# Sheet1.net
KiCad netlist of a schematic drawn in Altium Designer
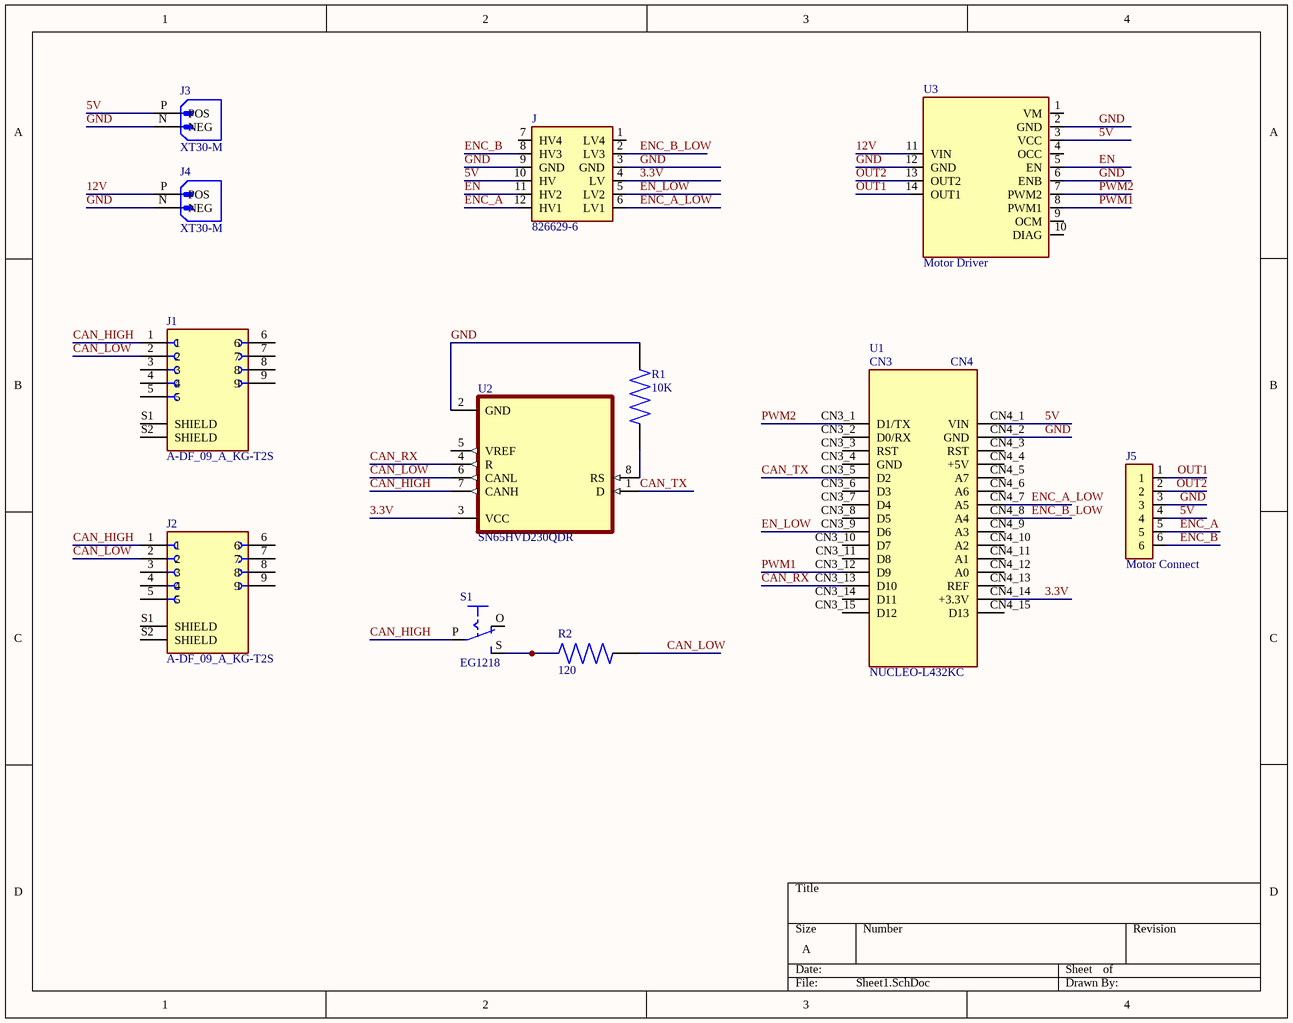
[diagram p0: Sheet1.SchDoc]

(export (version "E")
  (design (tool "Eeschema 10.0.6"))
  (components
    (comp (ref "J")
      (value "826629-6")
      (footprint "Level Converter:HDRV6W63P254_6X1_1524X250X950")
      (description "Conn Unshrouded Header HDR 6 POS 2.54mm Solder ST Thru-Hole Automotive Carton")
      (fields (field (name "MF") "TE Connectivity"))
      (libsource (lib "Level Converter") (part "826629-6"))
    )
    (comp (ref "J1")
      (value "A-DF_09_A_KG-T2S")
      (footprint "ASSMANN_A-DF_09_A_KG-T2S")
      (description "9 Position D-Sub Receptacle, Female Sockets Connector")
      (fields (field (name "MF") "Assmann WSW") (field (name "MP") "A-DF 09 A/KG-T2S"))
      (libsource (lib "A-DF_09_A_KG-T2S") (part "A-DF_09_A_KG-T2S"))
    )
    (comp (ref "J2")
      (value "A-DF_09_A_KG-T2S")
      (footprint "ASSMANN_A-DF_09_A_KG-T2S")
      (description "9 Position D-Sub Receptacle, Female Sockets Connector")
      (fields (field (name "MF") "Assmann WSW") (field (name "MP") "A-DF 09 A/KG-T2S"))
      (libsource (lib "A-DF_09_A_KG-T2S") (part "A-DF_09_A_KG-T2S"))
    )
    (comp (ref "J3")
      (value "XT30-M")
      (footprint "AMASS_XT60-M")
      (description "Plug; DC supply; XT60; male; PIN: 2; for cable; soldered; 30A; 500V")
      (fields (field (name "MP") "XT60-M") (field (name "MF") "AMASS"))
      (libsource (lib "XT30-M") (part "XT30-M"))
    )
    (comp (ref "J4")
      (value "XT30-M")
      (footprint "AMASS_XT60-M")
      (description "Plug; DC supply; XT60; male; PIN: 2; for cable; soldered; 30A; 500V")
      (fields (field (name "MP") "XT60-M") (field (name "MF") "AMASS"))
      (libsource (lib "XT30-M") (part "XT30-M"))
    )
    (comp (ref "J5")
      (value "Motor Connect")
      (footprint "HDRV6W63P254_6X1_1524X250X950")
      (description "Conn Unshrouded Header HDR 6 POS 2.54mm Solder ST Thru-Hole Automotive Carton")
      (fields (field (name "MP") "826629-6") (field (name "MF") "TE Connectivity"))
      (libsource (lib "826629-6") (part "826629-6"))
    )
    (comp (ref "R1")
      (value "10K")
      (footprint "RESC3216X65N:RESC3216X65N")
      (fields (field (name "MP") "KTR18EZPF9530"))
      (libsource (lib "KTR18EZPF9530") (part "KTR18EZPF9530"))
    )
    (comp (ref "R2")
      (value "120")
      (footprint "RESC3216X65N:RESC3216X65N")
      (fields (field (name "MP") "KTR18EZPF9530"))
      (libsource (lib "KTR18EZPF9530") (part "KTR18EZPF9530"))
    )
    (comp (ref "S1") (value "EG1218") (footprint "EG1218:EG1218") (libsource (lib "EG1218") (part "EG1218")))
    (comp (ref "U1")
      (value "NUCLEO-L432KC")
      (footprint "MODULE_NUCLEO-L432KC")
      (description "STM32 Nucleo-32 development board with STM32L432KC MCU, supports Arduino connectivity")
      (libsource (lib "NUCLEO-L432KC") (part "NUCLEO-L432KC"))
    )
    (comp (ref "U2")
      (value "SN65HVD230QDR")
      (footprint "SOIC127P599X175-8N")
      (description "3.3-V CAN Transceiver with Standby Mode 8-SOIC -40 to 125")
      (fields (field (name "MF") "Texas Instruments"))
      (libsource (lib "SN65HVD230QDR") (part "SN65HVD230QDR"))
    )
    (comp (ref "U3")
      (value "Motor Driver")
      (footprint "SnapEDApcb:TE_826629-8")
      (description "Conn Unshrouded Header HDR 8 POS 2.54mm Solder ST Thru-Hole Automotive Box")
      (fields (field (name "MP") "826629-8") (field (name "MF") "TE Connectivity"))
      (libsource (lib "Pololu Motor Driver") (part "826629-8"))
    )
  )
  (nets
    (net (code "1") (name "/3.3V") (class "Default")
      (node (ref "J") (pin "4") (pinfunction "LV_4") (pintype "passive"))
      (node (ref "U1") (pin "CN4_14") (pinfunction "+3.3V_CN4_14") (pintype "power_in"))
      (node (ref "U2") (pin "3") (pinfunction "VCC_3") (pintype "power_in"))
    )
    (net (code "2") (name "/5V") (class "Default")
      (node (ref "J") (pin "10") (pinfunction "HV_10") (pintype "passive"))
      (node (ref "J3") (pin "P") (pinfunction "POS_P") (pintype "passive"))
      (node (ref "J5") (pin "4") (pinfunction "4_4") (pintype "passive"))
      (node (ref "U1") (pin "CN4_1") (pinfunction "VIN_CN4_1") (pintype "power_in"))
      (node (ref "U3") (pin "3") (pinfunction "VCC_3") (pintype "passive"))
    )
    (net (code "3") (name "/12V") (class "Default")
      (node (ref "J4") (pin "P") (pinfunction "POS_P") (pintype "passive"))
      (node (ref "U3") (pin "11") (pinfunction "VIN_11") (pintype "passive"))
    )
    (net (code "4") (name "/CAN_HIGH") (class "Default")
      (node (ref "J1") (pin "1") (pinfunction "1_1") (pintype "passive"))
      (node (ref "J2") (pin "1") (pinfunction "1_1") (pintype "passive"))
      (node (ref "S1") (pin "P") (pinfunction "P_P") (pintype "passive"))
      (node (ref "U2") (pin "7") (pinfunction "CANH_7") (pintype "output"))
    )
    (net (code "5") (name "/CAN_LOW") (class "Default")
      (node (ref "J1") (pin "2") (pinfunction "2_2") (pintype "passive"))
      (node (ref "J2") (pin "2") (pinfunction "2_2") (pintype "passive"))
      (node (ref "R2") (pin "1") (pinfunction "1_1") (pintype "passive"))
      (node (ref "U2") (pin "6") (pinfunction "CANL_6") (pintype "output"))
    )
    (net (code "6") (name "/CAN_RX") (class "Default")
      (node (ref "U1") (pin "CN3_13") (pinfunction "D10_CN3_13") (pintype "passive"))
      (node (ref "U2") (pin "4") (pinfunction "R_4") (pintype "output"))
    )
    (net (code "7") (name "/CAN_TX") (class "Default")
      (node (ref "U1") (pin "CN3_5") (pinfunction "D2_CN3_5") (pintype "power_in"))
      (node (ref "U2") (pin "1") (pinfunction "D_1") (pintype "input"))
    )
    (net (code "8") (name "/EN") (class "Default")
      (node (ref "J") (pin "11") (pinfunction "HV2_11") (pintype "passive"))
      (node (ref "U3") (pin "5") (pinfunction "EN_5") (pintype "passive"))
    )
    (net (code "9") (name "/ENC_A") (class "Default")
      (node (ref "J") (pin "12") (pinfunction "HV1_12") (pintype "passive"))
      (node (ref "J5") (pin "5") (pinfunction "5_5") (pintype "passive"))
    )
    (net (code "10") (name "/ENC_A_LOW") (class "Default")
      (node (ref "J") (pin "6") (pinfunction "LV1_6") (pintype "passive"))
      (node (ref "U1") (pin "CN4_7") (pinfunction "A5_CN4_7") (pintype "passive"))
    )
    (net (code "11") (name "/ENC_B") (class "Default")
      (node (ref "J") (pin "8") (pinfunction "HV3_8") (pintype "passive"))
      (node (ref "J5") (pin "6") (pinfunction "6_6") (pintype "passive"))
    )
    (net (code "12") (name "/ENC_B_LOW") (class "Default")
      (node (ref "J") (pin "2") (pinfunction "LV3_2") (pintype "passive"))
      (node (ref "U1") (pin "CN4_8") (pinfunction "A4_CN4_8") (pintype "passive"))
    )
    (net (code "13") (name "/EN_LOW") (class "Default")
      (node (ref "J") (pin "5") (pinfunction "LV2_5") (pintype "passive"))
      (node (ref "U1") (pin "CN3_9") (pinfunction "D6_CN3_9") (pintype "power_in"))
    )
    (net (code "14") (name "/GND") (class "Default")
      (node (ref "J") (pin "3") (pinfunction "GND_3") (pintype "passive"))
      (node (ref "J") (pin "9") (pinfunction "GND_9") (pintype "passive"))
      (node (ref "J3") (pin "N") (pinfunction "NEG_N") (pintype "passive"))
      (node (ref "J4") (pin "N") (pinfunction "NEG_N") (pintype "passive"))
      (node (ref "J5") (pin "3") (pinfunction "3_3") (pintype "passive"))
      (node (ref "R1") (pin "2") (pinfunction "2_2") (pintype "passive"))
      (node (ref "U1") (pin "CN4_2") (pinfunction "GND_CN4_2") (pintype "power_in"))
      (node (ref "U2") (pin "2") (pinfunction "GND_2") (pintype "power_in"))
      (node (ref "U3") (pin "12") (pinfunction "GND_12") (pintype "passive"))
      (node (ref "U3") (pin "2") (pinfunction "GND_2") (pintype "passive"))
      (node (ref "U3") (pin "6") (pinfunction "ENB_6") (pintype "passive"))
    )
    (net (code "15") (name "/OUT1") (class "Default")
      (node (ref "J5") (pin "1") (pinfunction "1_1") (pintype "passive"))
      (node (ref "U3") (pin "14") (pinfunction "OUT1_14") (pintype "passive"))
    )
    (net (code "16") (name "/OUT2") (class "Default")
      (node (ref "J5") (pin "2") (pinfunction "2_2") (pintype "passive"))
      (node (ref "U3") (pin "13") (pinfunction "OUT2_13") (pintype "passive"))
    )
    (net (code "17") (name "/PWM1") (class "Default")
      (node (ref "U1") (pin "CN3_12") (pinfunction "D9_CN3_12") (pintype "power_in"))
      (node (ref "U3") (pin "8") (pinfunction "PWM1_8") (pintype "passive"))
    )
    (net (code "18") (name "/PWM2") (class "Default")
      (node (ref "U1") (pin "CN3_1") (pinfunction "D1/TX_CN3_1") (pintype "power_in"))
      (node (ref "U3") (pin "7") (pinfunction "PWM2_7") (pintype "passive"))
    )
    (net (code "19") (name "Net-(R2-Pad2)") (class "Default")
      (node (ref "R2") (pin "2") (pinfunction "2_2") (pintype "passive"))
      (node (ref "S1") (pin "S") (pinfunction "S_S") (pintype "passive"))
    )
    (net (code "20") (name "Net-(U2-RS)") (class "Default")
      (node (ref "R1") (pin "1") (pinfunction "1_1") (pintype "passive"))
      (node (ref "U2") (pin "8") (pinfunction "RS_8") (pintype "input"))
    )
    (net (code "21") (name "unconnected-(J-HV4-Pad7)") (class "Default")
      (node (ref "J") (pin "7") (pinfunction "HV4_7") (pintype "passive"))
    )
    (net (code "22") (name "unconnected-(J-LV4-Pad1)") (class "Default")
      (node (ref "J") (pin "1") (pinfunction "LV4_1") (pintype "passive"))
    )
    (net (code "23") (name "unconnected-(J1-Pad3)") (class "Default")
      (node (ref "J1") (pin "3") (pinfunction "3_3") (pintype "passive"))
    )
    (net (code "24") (name "unconnected-(J1-Pad4)") (class "Default")
      (node (ref "J1") (pin "4") (pinfunction "4_4") (pintype "passive"))
    )
    (net (code "25") (name "unconnected-(J1-Pad5)") (class "Default")
      (node (ref "J1") (pin "5") (pinfunction "5_5") (pintype "passive"))
    )
    (net (code "26") (name "unconnected-(J1-Pad6)") (class "Default")
      (node (ref "J1") (pin "6") (pinfunction "6_6") (pintype "passive"))
    )
    (net (code "27") (name "unconnected-(J1-Pad7)") (class "Default")
      (node (ref "J1") (pin "7") (pinfunction "7_7") (pintype "passive"))
    )
    (net (code "28") (name "unconnected-(J1-Pad8)") (class "Default")
      (node (ref "J1") (pin "8") (pinfunction "8_8") (pintype "passive"))
    )
    (net (code "29") (name "unconnected-(J1-Pad9)") (class "Default")
      (node (ref "J1") (pin "9") (pinfunction "9_9") (pintype "passive"))
    )
    (net (code "30") (name "unconnected-(J1-SHIELD-PadS1)") (class "Default")
      (node (ref "J1") (pin "S1") (pinfunction "SHIELD_S1") (pintype "passive"))
    )
    (net (code "31") (name "unconnected-(J1-SHIELD-PadS2)") (class "Default")
      (node (ref "J1") (pin "S2") (pinfunction "SHIELD_S2") (pintype "passive"))
    )
    (net (code "32") (name "unconnected-(J2-Pad3)") (class "Default")
      (node (ref "J2") (pin "3") (pinfunction "3_3") (pintype "passive"))
    )
    (net (code "33") (name "unconnected-(J2-Pad4)") (class "Default")
      (node (ref "J2") (pin "4") (pinfunction "4_4") (pintype "passive"))
    )
    (net (code "34") (name "unconnected-(J2-Pad5)") (class "Default")
      (node (ref "J2") (pin "5") (pinfunction "5_5") (pintype "passive"))
    )
    (net (code "35") (name "unconnected-(J2-Pad6)") (class "Default")
      (node (ref "J2") (pin "6") (pinfunction "6_6") (pintype "passive"))
    )
    (net (code "36") (name "unconnected-(J2-Pad7)") (class "Default")
      (node (ref "J2") (pin "7") (pinfunction "7_7") (pintype "passive"))
    )
    (net (code "37") (name "unconnected-(J2-Pad8)") (class "Default")
      (node (ref "J2") (pin "8") (pinfunction "8_8") (pintype "passive"))
    )
    (net (code "38") (name "unconnected-(J2-Pad9)") (class "Default")
      (node (ref "J2") (pin "9") (pinfunction "9_9") (pintype "passive"))
    )
    (net (code "39") (name "unconnected-(J2-SHIELD-PadS1)") (class "Default")
      (node (ref "J2") (pin "S1") (pinfunction "SHIELD_S1") (pintype "passive"))
    )
    (net (code "40") (name "unconnected-(J2-SHIELD-PadS2)") (class "Default")
      (node (ref "J2") (pin "S2") (pinfunction "SHIELD_S2") (pintype "passive"))
    )
    (net (code "41") (name "unconnected-(S1-PadO)") (class "Default")
      (node (ref "S1") (pin "O") (pinfunction "O_O") (pintype "passive"))
    )
    (net (code "42") (name "unconnected-(U1-+5V-PadCN4_4)") (class "Default")
      (node (ref "U1") (pin "CN4_4") (pinfunction "+5V_CN4_4") (pintype "power_in"))
    )
    (net (code "43") (name "unconnected-(U1-A0-PadCN4_12)") (class "Default")
      (node (ref "U1") (pin "CN4_12") (pinfunction "A0_CN4_12") (pintype "passive"))
    )
    (net (code "44") (name "unconnected-(U1-A1-PadCN4_11)") (class "Default")
      (node (ref "U1") (pin "CN4_11") (pinfunction "A1_CN4_11") (pintype "passive"))
    )
    (net (code "45") (name "unconnected-(U1-A2-PadCN4_10)") (class "Default")
      (node (ref "U1") (pin "CN4_10") (pinfunction "A2_CN4_10") (pintype "passive"))
    )
    (net (code "46") (name "unconnected-(U1-A3-PadCN4_9)") (class "Default")
      (node (ref "U1") (pin "CN4_9") (pinfunction "A3_CN4_9") (pintype "passive"))
    )
    (net (code "47") (name "unconnected-(U1-A6-PadCN4_6)") (class "Default")
      (node (ref "U1") (pin "CN4_6") (pinfunction "A6_CN4_6") (pintype "passive"))
    )
    (net (code "48") (name "unconnected-(U1-A7-PadCN4_5)") (class "Default")
      (node (ref "U1") (pin "CN4_5") (pinfunction "A7_CN4_5") (pintype "passive"))
    )
    (net (code "49") (name "unconnected-(U1-D0{slash}RX-PadCN3_2)") (class "Default")
      (node (ref "U1") (pin "CN3_2") (pinfunction "D0/RX_CN3_2") (pintype "power_in"))
    )
    (net (code "50") (name "unconnected-(U1-D3-PadCN3_6)") (class "Default")
      (node (ref "U1") (pin "CN3_6") (pinfunction "D3_CN3_6") (pintype "power_in"))
    )
    (net (code "51") (name "unconnected-(U1-D4-PadCN3_7)") (class "Default")
      (node (ref "U1") (pin "CN3_7") (pinfunction "D4_CN3_7") (pintype "power_in"))
    )
    (net (code "52") (name "unconnected-(U1-D5-PadCN3_8)") (class "Default")
      (node (ref "U1") (pin "CN3_8") (pinfunction "D5_CN3_8") (pintype "power_in"))
    )
    (net (code "53") (name "unconnected-(U1-D7-PadCN3_10)") (class "Default")
      (node (ref "U1") (pin "CN3_10") (pinfunction "D7_CN3_10") (pintype "power_in"))
    )
    (net (code "54") (name "unconnected-(U1-D8-PadCN3_11)") (class "Default")
      (node (ref "U1") (pin "CN3_11") (pinfunction "D8_CN3_11") (pintype "power_in"))
    )
    (net (code "55") (name "unconnected-(U1-D11-PadCN3_14)") (class "Default")
      (node (ref "U1") (pin "CN3_14") (pinfunction "D11_CN3_14") (pintype "power_in"))
    )
    (net (code "56") (name "unconnected-(U1-D12-PadCN3_15)") (class "Default")
      (node (ref "U1") (pin "CN3_15") (pinfunction "D12_CN3_15") (pintype "power_in"))
    )
    (net (code "57") (name "unconnected-(U1-D13-PadCN4_15)") (class "Default")
      (node (ref "U1") (pin "CN4_15") (pinfunction "D13_CN4_15") (pintype "power_in"))
    )
    (net (code "58") (name "unconnected-(U1-GND-PadCN3_4)") (class "Default")
      (node (ref "U1") (pin "CN3_4") (pinfunction "GND_CN3_4") (pintype "power_in"))
    )
    (net (code "59") (name "unconnected-(U1-REF-PadCN4_13)") (class "Default")
      (node (ref "U1") (pin "CN4_13") (pinfunction "REF_CN4_13") (pintype "passive"))
    )
    (net (code "60") (name "unconnected-(U1-RST-PadCN3_3)") (class "Default")
      (node (ref "U1") (pin "CN3_3") (pinfunction "RST_CN3_3") (pintype "power_in"))
    )
    (net (code "61") (name "unconnected-(U1-RST-PadCN4_3)") (class "Default")
      (node (ref "U1") (pin "CN4_3") (pinfunction "RST_CN4_3") (pintype "passive"))
    )
    (net (code "62") (name "unconnected-(U2-VREF-Pad5)") (class "Default")
      (node (ref "U2") (pin "5") (pinfunction "VREF_5") (pintype "output"))
    )
    (net (code "63") (name "unconnected-(U3-DIAG-Pad10)") (class "Default")
      (node (ref "U3") (pin "10") (pinfunction "DIAG_10") (pintype "passive"))
    )
    (net (code "64") (name "unconnected-(U3-OCC-Pad4)") (class "Default")
      (node (ref "U3") (pin "4") (pinfunction "OCC_4") (pintype "passive"))
    )
    (net (code "65") (name "unconnected-(U3-OCM-Pad9)") (class "Default")
      (node (ref "U3") (pin "9") (pinfunction "OCM_9") (pintype "passive"))
    )
    (net (code "66") (name "unconnected-(U3-VM-Pad1)") (class "Default")
      (node (ref "U3") (pin "1") (pinfunction "VM_1") (pintype "passive"))
    )
  )
)
